# NAND.net
KiCad netlist of a schematic drawn in Altium Designer
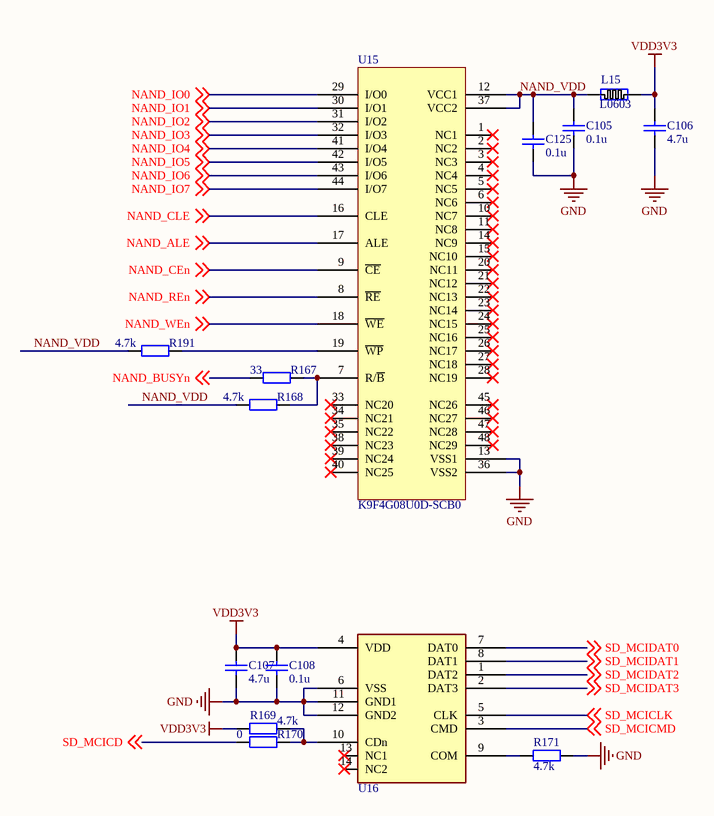
[diagram p0: NAND.SchDoc]

(export (version "E")
  (design (tool "Eeschema 10.0.6"))
  (components
    (comp (ref "C105")
      (value "0.1u")
      (footprint "C0603")
      (description "0603 Capacitor without Polarity")
      (libsource (lib "lpc2368") (part "CAP0603"))
    )
    (comp (ref "C106")
      (value "4.7u")
      (footprint "C0603")
      (description "0603 Capacitor without Polarity")
      (libsource (lib "lpc2368") (part "CAP0603"))
    )
    (comp (ref "C107")
      (value "4.7u")
      (footprint "C0603")
      (description "0603 Capacitor without Polarity")
      (libsource (lib "lpc2368") (part "CAP0603"))
    )
    (comp (ref "C108")
      (value "0.1u")
      (footprint "C0603")
      (description "0603 Capacitor without Polarity")
      (libsource (lib "lpc2368") (part "CAP0603"))
    )
    (comp (ref "C125")
      (value "0.1u")
      (footprint "C0603")
      (description "0603 Capacitor without Polarity")
      (libsource (lib "lpc2368") (part "CAP0603"))
    )
    (comp (ref "L15")
      (value "L0603")
      (footprint "L0603")
      (description "0603 Inductor")
      (libsource (lib "lpc2368") (part "L0603"))
    )
    (comp (ref "R167")
      (value "33")
      (footprint "R0603")
      (description "0603 Resistor")
      (libsource (lib "lpc2368") (part "RES0603"))
    )
    (comp (ref "R168")
      (value "4.7k")
      (footprint "R0603")
      (description "0603 Resistor")
      (libsource (lib "") (part "RES0603_1"))
    )
    (comp (ref "R169")
      (value "4.7k")
      (footprint "R0603")
      (description "0603 Resistor")
      (libsource (lib "lpc2368") (part "RES0603"))
    )
    (comp (ref "R170")
      (value "0")
      (footprint "R0603")
      (description "0603 Resistor")
      (libsource (lib "lpc2368") (part "RES0603"))
    )
    (comp (ref "R171")
      (value "4.7k")
      (footprint "R0603")
      (description "0603 Resistor")
      (libsource (lib "lpc2368") (part "RES0603"))
    )
    (comp (ref "R191")
      (value "4.7k")
      (footprint "R0603")
      (description "0603 Resistor")
      (libsource (lib "") (part "RES0603_1"))
    )
    (comp (ref "U15")
      (value "K9F4G08U0D-SCB0")
      (footprint "SOP48-I20-765")
      (description "NAND FLASH")
      (libsource (lib "lpc2368") (part "K9F4G08U0D-SCB0"))
    )
    (comp (ref "U16")
      (value "TF CON")
      (footprint "TF-14")
      (description "TF Card Connector")
      (libsource (lib "lpc2368") (part "TF CON"))
    )
  )
  (nets
    (net (code "1") (name "/NAND_VDD") (class "Default")
      (node (ref "C105") (pin "2") (pinfunction "2_2") (pintype "passive"))
      (node (ref "C125") (pin "2") (pinfunction "2_2") (pintype "passive"))
      (node (ref "L15") (pin "1") (pinfunction "1_1") (pintype "passive"))
      (node (ref "R168") (pin "2") (pinfunction "2_2") (pintype "passive"))
      (node (ref "R191") (pin "2") (pinfunction "2_2") (pintype "passive"))
      (node (ref "U15") (pin "12") (pinfunction "VCC1_12") (pintype "power_in"))
      (node (ref "U15") (pin "37") (pinfunction "VCC2_37") (pintype "power_in"))
    )
    (net (code "2") (name "GND") (class "Default")
      (node (ref "C105") (pin "1") (pinfunction "1_1") (pintype "passive"))
      (node (ref "C106") (pin "1") (pinfunction "1_1") (pintype "passive"))
      (node (ref "C107") (pin "1") (pinfunction "1_1") (pintype "passive"))
      (node (ref "C108") (pin "1") (pinfunction "1_1") (pintype "passive"))
      (node (ref "C125") (pin "1") (pinfunction "1_1") (pintype "passive"))
      (node (ref "R171") (pin "2") (pinfunction "2_2") (pintype "passive"))
      (node (ref "U15") (pin "13") (pinfunction "VSS1_13") (pintype "power_in"))
      (node (ref "U15") (pin "36") (pinfunction "VSS2_36") (pintype "power_in"))
      (node (ref "U16") (pin "11") (pinfunction "GND1_11") (pintype "passive"))
      (node (ref "U16") (pin "12") (pinfunction "GND2_12") (pintype "passive"))
      (node (ref "U16") (pin "6") (pinfunction "VSS_6") (pintype "passive"))
    )
    (net (code "3") (name "NAND_ALE") (class "Default")
      (node (ref "U15") (pin "17") (pinfunction "ALE_17") (pintype "passive"))
    )
    (net (code "4") (name "NAND_BUSYn") (class "Default")
      (node (ref "R167") (pin "1") (pinfunction "1_1") (pintype "passive"))
    )
    (net (code "5") (name "NAND_CEn") (class "Default")
      (node (ref "U15") (pin "9") (pinfunction "~{CE}_9") (pintype "passive"))
    )
    (net (code "6") (name "NAND_CLE") (class "Default")
      (node (ref "U15") (pin "16") (pinfunction "CLE_16") (pintype "passive"))
    )
    (net (code "7") (name "NAND_IO0") (class "Default")
      (node (ref "U15") (pin "29") (pinfunction "I/O0_29") (pintype "passive"))
    )
    (net (code "8") (name "NAND_IO1") (class "Default")
      (node (ref "U15") (pin "30") (pinfunction "I/O1_30") (pintype "passive"))
    )
    (net (code "9") (name "NAND_IO2") (class "Default")
      (node (ref "U15") (pin "31") (pinfunction "I/O2_31") (pintype "passive"))
    )
    (net (code "10") (name "NAND_IO3") (class "Default")
      (node (ref "U15") (pin "32") (pinfunction "I/O3_32") (pintype "passive"))
    )
    (net (code "11") (name "NAND_IO4") (class "Default")
      (node (ref "U15") (pin "41") (pinfunction "I/O4_41") (pintype "passive"))
    )
    (net (code "12") (name "NAND_IO5") (class "Default")
      (node (ref "U15") (pin "42") (pinfunction "I/O5_42") (pintype "passive"))
    )
    (net (code "13") (name "NAND_IO6") (class "Default")
      (node (ref "U15") (pin "43") (pinfunction "I/O6_43") (pintype "passive"))
    )
    (net (code "14") (name "NAND_IO7") (class "Default")
      (node (ref "U15") (pin "44") (pinfunction "I/O7_44") (pintype "passive"))
    )
    (net (code "15") (name "NAND_REn") (class "Default")
      (node (ref "U15") (pin "8") (pinfunction "~{RE}_8") (pintype "passive"))
    )
    (net (code "16") (name "NAND_WEn") (class "Default")
      (node (ref "U15") (pin "18") (pinfunction "~{WE}_18") (pintype "passive"))
    )
    (net (code "17") (name "Net-(U15-R{slash}~{B})") (class "Default")
      (node (ref "R167") (pin "2") (pinfunction "2_2") (pintype "passive"))
      (node (ref "R168") (pin "1") (pinfunction "1_1") (pintype "passive"))
      (node (ref "U15") (pin "7") (pinfunction "R/~{B}_7") (pintype "passive"))
    )
    (net (code "18") (name "Net-(U15-~{WP})") (class "Default")
      (node (ref "R191") (pin "1") (pinfunction "1_1") (pintype "passive"))
      (node (ref "U15") (pin "19") (pinfunction "~{WP}_19") (pintype "passive"))
    )
    (net (code "19") (name "Net-(U16-CDn)") (class "Default")
      (node (ref "R169") (pin "2") (pinfunction "2_2") (pintype "passive"))
      (node (ref "R170") (pin "2") (pinfunction "2_2") (pintype "passive"))
      (node (ref "U16") (pin "10") (pinfunction "CDn_10") (pintype "passive"))
    )
    (net (code "20") (name "Net-(U16-COM)") (class "Default")
      (node (ref "R171") (pin "1") (pinfunction "1_1") (pintype "passive"))
      (node (ref "U16") (pin "9") (pinfunction "COM_9") (pintype "passive"))
    )
    (net (code "21") (name "SD_MCICD") (class "Default")
      (node (ref "R170") (pin "1") (pinfunction "1_1") (pintype "passive"))
    )
    (net (code "22") (name "SD_MCICLK") (class "Default")
      (node (ref "U16") (pin "5") (pinfunction "CLK_5") (pintype "passive"))
    )
    (net (code "23") (name "SD_MCICMD") (class "Default")
      (node (ref "U16") (pin "3") (pinfunction "CMD_3") (pintype "passive"))
    )
    (net (code "24") (name "SD_MCIDAT0") (class "Default")
      (node (ref "U16") (pin "7") (pinfunction "DAT0_7") (pintype "passive"))
    )
    (net (code "25") (name "SD_MCIDAT1") (class "Default")
      (node (ref "U16") (pin "8") (pinfunction "DAT1_8") (pintype "passive"))
    )
    (net (code "26") (name "SD_MCIDAT2") (class "Default")
      (node (ref "U16") (pin "1") (pinfunction "DAT2_1") (pintype "passive"))
    )
    (net (code "27") (name "SD_MCIDAT3") (class "Default")
      (node (ref "U16") (pin "2") (pinfunction "DAT3_2") (pintype "passive"))
    )
    (net (code "28") (name "VDD3V3") (class "Default")
      (node (ref "C106") (pin "2") (pinfunction "2_2") (pintype "passive"))
      (node (ref "C107") (pin "2") (pinfunction "2_2") (pintype "passive"))
      (node (ref "C108") (pin "2") (pinfunction "2_2") (pintype "passive"))
      (node (ref "L15") (pin "2") (pinfunction "2_2") (pintype "passive"))
      (node (ref "R169") (pin "1") (pinfunction "1_1") (pintype "passive"))
      (node (ref "U16") (pin "4") (pinfunction "VDD_4") (pintype "passive"))
    )
    (net (code "29") (name "unconnected-(U15-NC1-Pad1)") (class "Default")
      (node (ref "U15") (pin "1") (pinfunction "NC1_1") (pintype "passive+no_connect"))
    )
    (net (code "30") (name "unconnected-(U15-NC2-Pad2)") (class "Default")
      (node (ref "U15") (pin "2") (pinfunction "NC2_2") (pintype "passive+no_connect"))
    )
    (net (code "31") (name "unconnected-(U15-NC3-Pad3)") (class "Default")
      (node (ref "U15") (pin "3") (pinfunction "NC3_3") (pintype "passive+no_connect"))
    )
    (net (code "32") (name "unconnected-(U15-NC4-Pad4)") (class "Default")
      (node (ref "U15") (pin "4") (pinfunction "NC4_4") (pintype "passive+no_connect"))
    )
    (net (code "33") (name "unconnected-(U15-NC5-Pad5)") (class "Default")
      (node (ref "U15") (pin "5") (pinfunction "NC5_5") (pintype "passive+no_connect"))
    )
    (net (code "34") (name "unconnected-(U15-NC6-Pad6)") (class "Default")
      (node (ref "U15") (pin "6") (pinfunction "NC6_6") (pintype "passive+no_connect"))
    )
    (net (code "35") (name "unconnected-(U15-NC7-Pad10)") (class "Default")
      (node (ref "U15") (pin "10") (pinfunction "NC7_10") (pintype "passive+no_connect"))
    )
    (net (code "36") (name "unconnected-(U15-NC8-Pad11)") (class "Default")
      (node (ref "U15") (pin "11") (pinfunction "NC8_11") (pintype "passive+no_connect"))
    )
    (net (code "37") (name "unconnected-(U15-NC9-Pad14)") (class "Default")
      (node (ref "U15") (pin "14") (pinfunction "NC9_14") (pintype "passive+no_connect"))
    )
    (net (code "38") (name "unconnected-(U15-NC10-Pad15)") (class "Default")
      (node (ref "U15") (pin "15") (pinfunction "NC10_15") (pintype "passive+no_connect"))
    )
    (net (code "39") (name "unconnected-(U15-NC11-Pad20)") (class "Default")
      (node (ref "U15") (pin "20") (pinfunction "NC11_20") (pintype "passive+no_connect"))
    )
    (net (code "40") (name "unconnected-(U15-NC12-Pad21)") (class "Default")
      (node (ref "U15") (pin "21") (pinfunction "NC12_21") (pintype "passive+no_connect"))
    )
    (net (code "41") (name "unconnected-(U15-NC13-Pad22)") (class "Default")
      (node (ref "U15") (pin "22") (pinfunction "NC13_22") (pintype "passive+no_connect"))
    )
    (net (code "42") (name "unconnected-(U15-NC14-Pad23)") (class "Default")
      (node (ref "U15") (pin "23") (pinfunction "NC14_23") (pintype "passive+no_connect"))
    )
    (net (code "43") (name "unconnected-(U15-NC15-Pad24)") (class "Default")
      (node (ref "U15") (pin "24") (pinfunction "NC15_24") (pintype "passive+no_connect"))
    )
    (net (code "44") (name "unconnected-(U15-NC16-Pad25)") (class "Default")
      (node (ref "U15") (pin "25") (pinfunction "NC16_25") (pintype "passive+no_connect"))
    )
    (net (code "45") (name "unconnected-(U15-NC17-Pad26)") (class "Default")
      (node (ref "U15") (pin "26") (pinfunction "NC17_26") (pintype "passive+no_connect"))
    )
    (net (code "46") (name "unconnected-(U15-NC18-Pad27)") (class "Default")
      (node (ref "U15") (pin "27") (pinfunction "NC18_27") (pintype "passive+no_connect"))
    )
    (net (code "47") (name "unconnected-(U15-NC19-Pad28)") (class "Default")
      (node (ref "U15") (pin "28") (pinfunction "NC19_28") (pintype "passive+no_connect"))
    )
    (net (code "48") (name "unconnected-(U15-NC20-Pad33)") (class "Default")
      (node (ref "U15") (pin "33") (pinfunction "NC20_33") (pintype "passive+no_connect"))
    )
    (net (code "49") (name "unconnected-(U15-NC21-Pad34)") (class "Default")
      (node (ref "U15") (pin "34") (pinfunction "NC21_34") (pintype "passive+no_connect"))
    )
    (net (code "50") (name "unconnected-(U15-NC22-Pad35)") (class "Default")
      (node (ref "U15") (pin "35") (pinfunction "NC22_35") (pintype "passive+no_connect"))
    )
    (net (code "51") (name "unconnected-(U15-NC23-Pad38)") (class "Default")
      (node (ref "U15") (pin "38") (pinfunction "NC23_38") (pintype "passive+no_connect"))
    )
    (net (code "52") (name "unconnected-(U15-NC24-Pad39)") (class "Default")
      (node (ref "U15") (pin "39") (pinfunction "NC24_39") (pintype "passive+no_connect"))
    )
    (net (code "53") (name "unconnected-(U15-NC25-Pad40)") (class "Default")
      (node (ref "U15") (pin "40") (pinfunction "NC25_40") (pintype "passive+no_connect"))
    )
    (net (code "54") (name "unconnected-(U15-NC26-Pad45)") (class "Default")
      (node (ref "U15") (pin "45") (pinfunction "NC26_45") (pintype "passive+no_connect"))
    )
    (net (code "55") (name "unconnected-(U15-NC27-Pad46)") (class "Default")
      (node (ref "U15") (pin "46") (pinfunction "NC27_46") (pintype "passive+no_connect"))
    )
    (net (code "56") (name "unconnected-(U15-NC28-Pad47)") (class "Default")
      (node (ref "U15") (pin "47") (pinfunction "NC28_47") (pintype "passive+no_connect"))
    )
    (net (code "57") (name "unconnected-(U15-NC29-Pad48)") (class "Default")
      (node (ref "U15") (pin "48") (pinfunction "NC29_48") (pintype "passive+no_connect"))
    )
    (net (code "58") (name "unconnected-(U16-NC1-Pad13)") (class "Default")
      (node (ref "U16") (pin "13") (pinfunction "NC1_13") (pintype "passive+no_connect"))
    )
    (net (code "59") (name "unconnected-(U16-NC2-Pad14)") (class "Default")
      (node (ref "U16") (pin "14") (pinfunction "NC2_14") (pintype "passive+no_connect"))
    )
  )
)
